# LED_MATRIX1.net
KiCad netlist of a schematic drawn in EAGLE
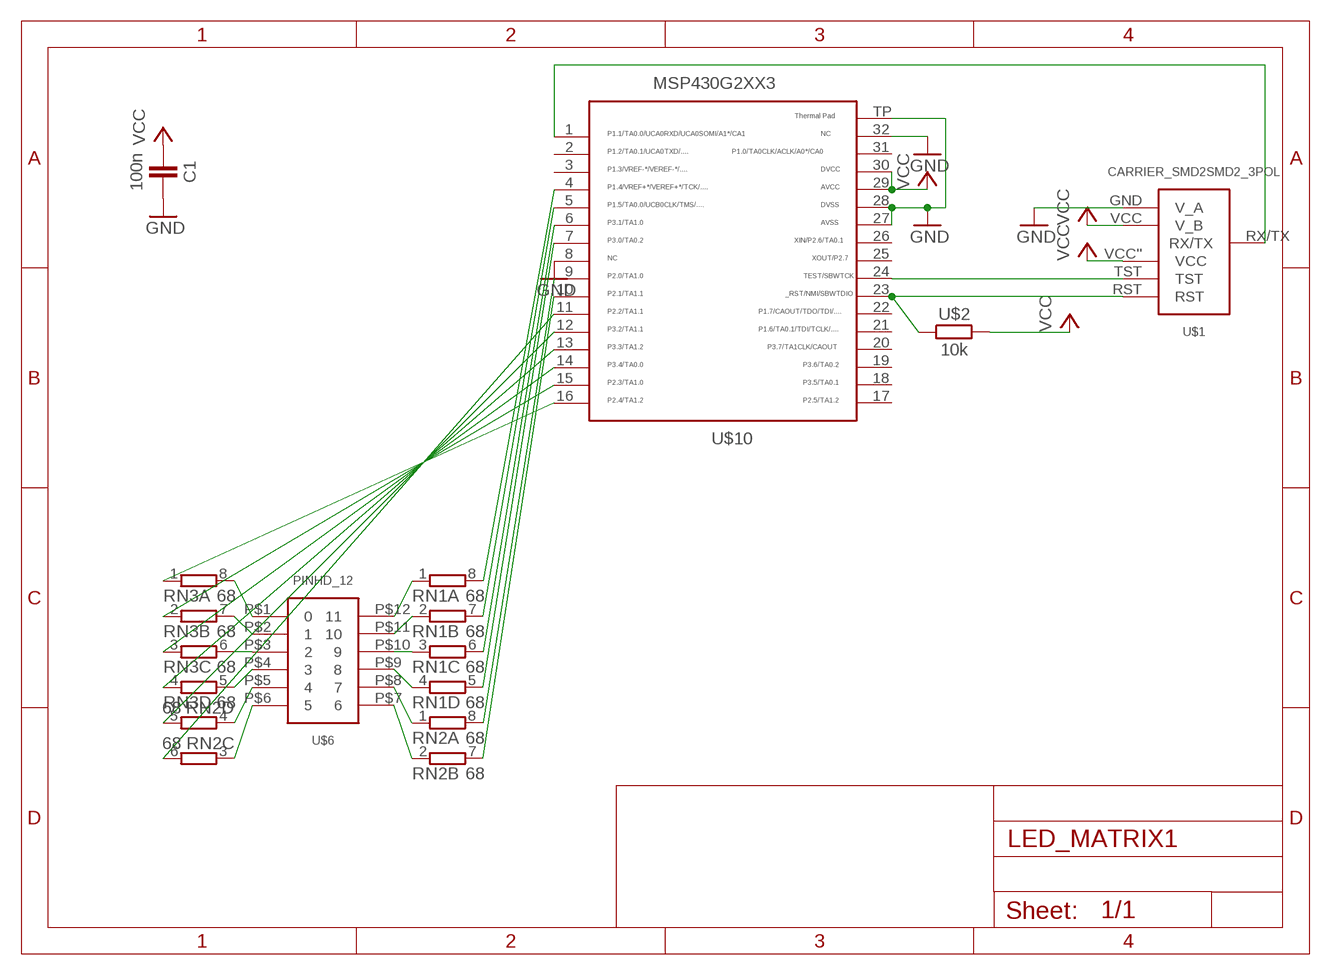
[diagram p0: schematic, sheet 1]

(export (version "E")
  (design (tool "Eeschema 10.0.6"))
  (components
    (comp (ref "C1")
      (value "100n")
      (footprint "eagle-import:603")
      (libsource (lib "eagle-import") (part "CAPACITOR"))
    )
    (comp (ref "RN1")
      (value "68")
      (footprint "eagle-import:0603-ARC")
      (libsource (lib "eagle-import") (part "4R-N0603-ARC"))
    )
    (comp (ref "RN2")
      (value "68")
      (footprint "eagle-import:0603-ARC")
      (libsource (lib "eagle-import") (part "4R-N0603-ARC"))
    )
    (comp (ref "RN3")
      (value "68")
      (footprint "eagle-import:0603-ARC")
      (libsource (lib "eagle-import") (part "4R-N0603-ARC"))
    )
    (comp (ref "U$1")
      (value "CARRIER_SMD2SMD2_3POL")
      (footprint "eagle-import:CARRIER_SMD2_3POL")
      (libsource (lib "eagle-import") (part "CARRIER_SMD2SMD2_3POL"))
    )
    (comp (ref "U$2")
      (value "10k")
      (footprint "eagle-import:603")
      (libsource (lib "eagle-import") (part "RESISTOR0603"))
    )
    (comp (ref "U$6")
      (value "PINHD_12")
      (footprint "eagle-import:FFC12_1MM")
      (libsource (lib "eagle-import") (part "PINHD_12"))
    )
    (comp (ref "U$10")
      (value "MSP430G2553")
      (footprint "eagle-import:QFN32")
      (libsource (lib "eagle-import") (part "MSP430G2553"))
    )
  )
  (nets
    (net (code "1") (name "GND") (class "Default")
      (node (ref "C1") (pin "2") (pinfunction "2_2") (pintype "passive"))
      (node (ref "U$1") (pin "GND") (pinfunction "V_A_GND") (pintype "bidirectional"))
      (node (ref "U$10") (pin "27") (pinfunction "27_27") (pintype "bidirectional"))
      (node (ref "U$10") (pin "28") (pinfunction "28_28") (pintype "bidirectional"))
      (node (ref "U$10") (pin "32") (pinfunction "32_32") (pintype "bidirectional"))
      (node (ref "U$10") (pin "8") (pinfunction "8_8") (pintype "bidirectional"))
      (node (ref "U$10") (pin "TP") (pinfunction "TP_TP") (pintype "bidirectional"))
    )
    (net (code "2") (name "Net-(RN1A-2)") (class "Default")
      (node (ref "RN1") (pin "8") (pinfunction "2_8") (pintype "passive"))
      (node (ref "U$10") (pin "4") (pinfunction "4_4") (pintype "bidirectional"))
    )
    (net (code "3") (name "Net-(RN1B-1)") (class "Default")
      (node (ref "RN1") (pin "2") (pinfunction "1_2") (pintype "passive"))
      (node (ref "U$6") (pin "P$11") (pinfunction "10_P$11") (pintype "bidirectional"))
    )
    (net (code "4") (name "Net-(RN1B-2)") (class "Default")
      (node (ref "RN1") (pin "7") (pinfunction "2_7") (pintype "passive"))
      (node (ref "U$10") (pin "5") (pinfunction "5_5") (pintype "bidirectional"))
    )
    (net (code "5") (name "Net-(RN1C-1)") (class "Default")
      (node (ref "RN1") (pin "3") (pinfunction "1_3") (pintype "passive"))
      (node (ref "U$6") (pin "P$10") (pinfunction "9_P$10") (pintype "bidirectional"))
    )
    (net (code "6") (name "Net-(RN1C-2)") (class "Default")
      (node (ref "RN1") (pin "6") (pinfunction "2_6") (pintype "passive"))
      (node (ref "U$10") (pin "6") (pinfunction "6_6") (pintype "bidirectional"))
    )
    (net (code "7") (name "Net-(RN1D-1)") (class "Default")
      (node (ref "RN1") (pin "4") (pinfunction "1_4") (pintype "passive"))
      (node (ref "U$6") (pin "P$9") (pinfunction "8_P$9") (pintype "bidirectional"))
    )
    (net (code "8") (name "Net-(RN1D-2)") (class "Default")
      (node (ref "RN1") (pin "5") (pinfunction "2_5") (pintype "passive"))
      (node (ref "U$10") (pin "7") (pinfunction "7_7") (pintype "bidirectional"))
    )
    (net (code "9") (name "Net-(RN2A-2)") (class "Default")
      (node (ref "RN2") (pin "8") (pinfunction "2_8") (pintype "passive"))
      (node (ref "U$10") (pin "9") (pinfunction "9_9") (pintype "bidirectional"))
    )
    (net (code "10") (name "Net-(RN2B-1)") (class "Default")
      (node (ref "RN2") (pin "2") (pinfunction "1_2") (pintype "passive"))
      (node (ref "U$6") (pin "P$7") (pinfunction "6_P$7") (pintype "bidirectional"))
    )
    (net (code "11") (name "Net-(RN2B-2)") (class "Default")
      (node (ref "RN2") (pin "7") (pinfunction "2_7") (pintype "passive"))
      (node (ref "U$10") (pin "10") (pinfunction "10_10") (pintype "bidirectional"))
    )
    (net (code "12") (name "Net-(RN2C-1)") (class "Default")
      (node (ref "RN2") (pin "3") (pinfunction "1_3") (pintype "passive"))
      (node (ref "U$6") (pin "P$6") (pinfunction "5_P$6") (pintype "bidirectional"))
    )
    (net (code "13") (name "Net-(RN2C-2)") (class "Default")
      (node (ref "RN2") (pin "6") (pinfunction "2_6") (pintype "passive"))
      (node (ref "U$10") (pin "11") (pinfunction "11_11") (pintype "bidirectional"))
    )
    (net (code "14") (name "Net-(RN2D-1)") (class "Default")
      (node (ref "RN2") (pin "4") (pinfunction "1_4") (pintype "passive"))
      (node (ref "U$6") (pin "P$5") (pinfunction "4_P$5") (pintype "bidirectional"))
    )
    (net (code "15") (name "Net-(RN2D-2)") (class "Default")
      (node (ref "RN2") (pin "5") (pinfunction "2_5") (pintype "passive"))
      (node (ref "U$10") (pin "12") (pinfunction "12_12") (pintype "bidirectional"))
    )
    (net (code "16") (name "Net-(RN3-Pad1)") (class "Default")
      (node (ref "RN3") (pin "1") (pinfunction "1_1") (pintype "passive"))
      (node (ref "U$10") (pin "16") (pinfunction "16_16") (pintype "bidirectional"))
    )
    (net (code "17") (name "Net-(RN3A-2)") (class "Default")
      (node (ref "RN3") (pin "8") (pinfunction "2_8") (pintype "passive"))
      (node (ref "U$6") (pin "P$1") (pinfunction "0_P$1") (pintype "bidirectional"))
    )
    (net (code "18") (name "Net-(RN3B-1)") (class "Default")
      (node (ref "RN3") (pin "2") (pinfunction "1_2") (pintype "passive"))
      (node (ref "U$10") (pin "15") (pinfunction "15_15") (pintype "bidirectional"))
    )
    (net (code "19") (name "Net-(RN3B-2)") (class "Default")
      (node (ref "RN3") (pin "7") (pinfunction "2_7") (pintype "passive"))
      (node (ref "U$6") (pin "P$2") (pinfunction "1_P$2") (pintype "bidirectional"))
    )
    (net (code "20") (name "Net-(RN3C-1)") (class "Default")
      (node (ref "RN3") (pin "3") (pinfunction "1_3") (pintype "passive"))
      (node (ref "U$10") (pin "14") (pinfunction "14_14") (pintype "bidirectional"))
    )
    (net (code "21") (name "Net-(RN3C-2)") (class "Default")
      (node (ref "RN3") (pin "6") (pinfunction "2_6") (pintype "passive"))
      (node (ref "U$6") (pin "P$3") (pinfunction "2_P$3") (pintype "bidirectional"))
    )
    (net (code "22") (name "Net-(RN3D-1)") (class "Default")
      (node (ref "RN3") (pin "4") (pinfunction "1_4") (pintype "passive"))
      (node (ref "U$10") (pin "13") (pinfunction "13_13") (pintype "bidirectional"))
    )
    (net (code "23") (name "Net-(RN3D-2)") (class "Default")
      (node (ref "RN3") (pin "5") (pinfunction "2_5") (pintype "passive"))
      (node (ref "U$6") (pin "P$4") (pinfunction "3_P$4") (pintype "bidirectional"))
    )
    (net (code "24") (name "Net-(U$1-PadRST)") (class "Default")
      (node (ref "U$1") (pin "RST") (pinfunction "RST_RST") (pintype "bidirectional"))
      (node (ref "U$10") (pin "23") (pinfunction "23_23") (pintype "bidirectional"))
      (node (ref "U$2") (pin "1") (pinfunction "1_1") (pintype "passive"))
    )
    (net (code "25") (name "Net-(U$1-PadRX{slash}TX)") (class "Default")
      (node (ref "U$1") (pin "RX/TX") (pinfunction "RX/TX_RX/TX") (pintype "bidirectional"))
      (node (ref "U$10") (pin "1") (pinfunction "1_1") (pintype "bidirectional"))
    )
    (net (code "26") (name "Net-(U$1-PadTST)") (class "Default")
      (node (ref "U$1") (pin "TST") (pinfunction "TST_TST") (pintype "bidirectional"))
      (node (ref "U$10") (pin "24") (pinfunction "24_24") (pintype "bidirectional"))
    )
    (net (code "27") (name "Net-(U$6-7)") (class "Default")
      (node (ref "RN2") (pin "1") (pinfunction "1_1") (pintype "passive"))
      (node (ref "U$6") (pin "P$8") (pinfunction "7_P$8") (pintype "bidirectional"))
    )
    (net (code "28") (name "Net-(U$6-11)") (class "Default")
      (node (ref "RN1") (pin "1") (pinfunction "1_1") (pintype "passive"))
      (node (ref "U$6") (pin "P$12") (pinfunction "11_P$12") (pintype "bidirectional"))
    )
    (net (code "29") (name "VCC") (class "Default")
      (node (ref "C1") (pin "1") (pinfunction "1_1") (pintype "passive"))
      (node (ref "U$1") (pin "VCC") (pinfunction "V_B_VCC") (pintype "bidirectional"))
      (node (ref "U$1") (pin "VCC''") (pinfunction "VCC_VCC''") (pintype "bidirectional"))
      (node (ref "U$10") (pin "29") (pinfunction "29_29") (pintype "bidirectional"))
      (node (ref "U$10") (pin "30") (pinfunction "30_30") (pintype "bidirectional"))
      (node (ref "U$2") (pin "2") (pinfunction "2_2") (pintype "passive"))
    )
    (net (code "30") (name "unconnected-(U$10-Pad2)") (class "Default")
      (node (ref "U$10") (pin "2") (pinfunction "2_2") (pintype "bidirectional"))
    )
    (net (code "31") (name "unconnected-(U$10-Pad3)") (class "Default")
      (node (ref "U$10") (pin "3") (pinfunction "3_3") (pintype "bidirectional"))
    )
    (net (code "32") (name "unconnected-(U$10-Pad17)") (class "Default")
      (node (ref "U$10") (pin "17") (pinfunction "17_17") (pintype "bidirectional"))
    )
    (net (code "33") (name "unconnected-(U$10-Pad18)") (class "Default")
      (node (ref "U$10") (pin "18") (pinfunction "18_18") (pintype "bidirectional"))
    )
    (net (code "34") (name "unconnected-(U$10-Pad19)") (class "Default")
      (node (ref "U$10") (pin "19") (pinfunction "19_19") (pintype "bidirectional"))
    )
    (net (code "35") (name "unconnected-(U$10-Pad20)") (class "Default")
      (node (ref "U$10") (pin "20") (pinfunction "20_20") (pintype "bidirectional"))
    )
    (net (code "36") (name "unconnected-(U$10-Pad21)") (class "Default")
      (node (ref "U$10") (pin "21") (pinfunction "21_21") (pintype "bidirectional"))
    )
    (net (code "37") (name "unconnected-(U$10-Pad22)") (class "Default")
      (node (ref "U$10") (pin "22") (pinfunction "22_22") (pintype "bidirectional"))
    )
    (net (code "38") (name "unconnected-(U$10-Pad25)") (class "Default")
      (node (ref "U$10") (pin "25") (pinfunction "25_25") (pintype "bidirectional"))
    )
    (net (code "39") (name "unconnected-(U$10-Pad26)") (class "Default")
      (node (ref "U$10") (pin "26") (pinfunction "26_26") (pintype "bidirectional"))
    )
    (net (code "40") (name "unconnected-(U$10-Pad31)") (class "Default")
      (node (ref "U$10") (pin "31") (pinfunction "31_31") (pintype "bidirectional"))
    )
  )
)
